# Y021.net
KiCad netlist of a schematic drawn in EAGLE
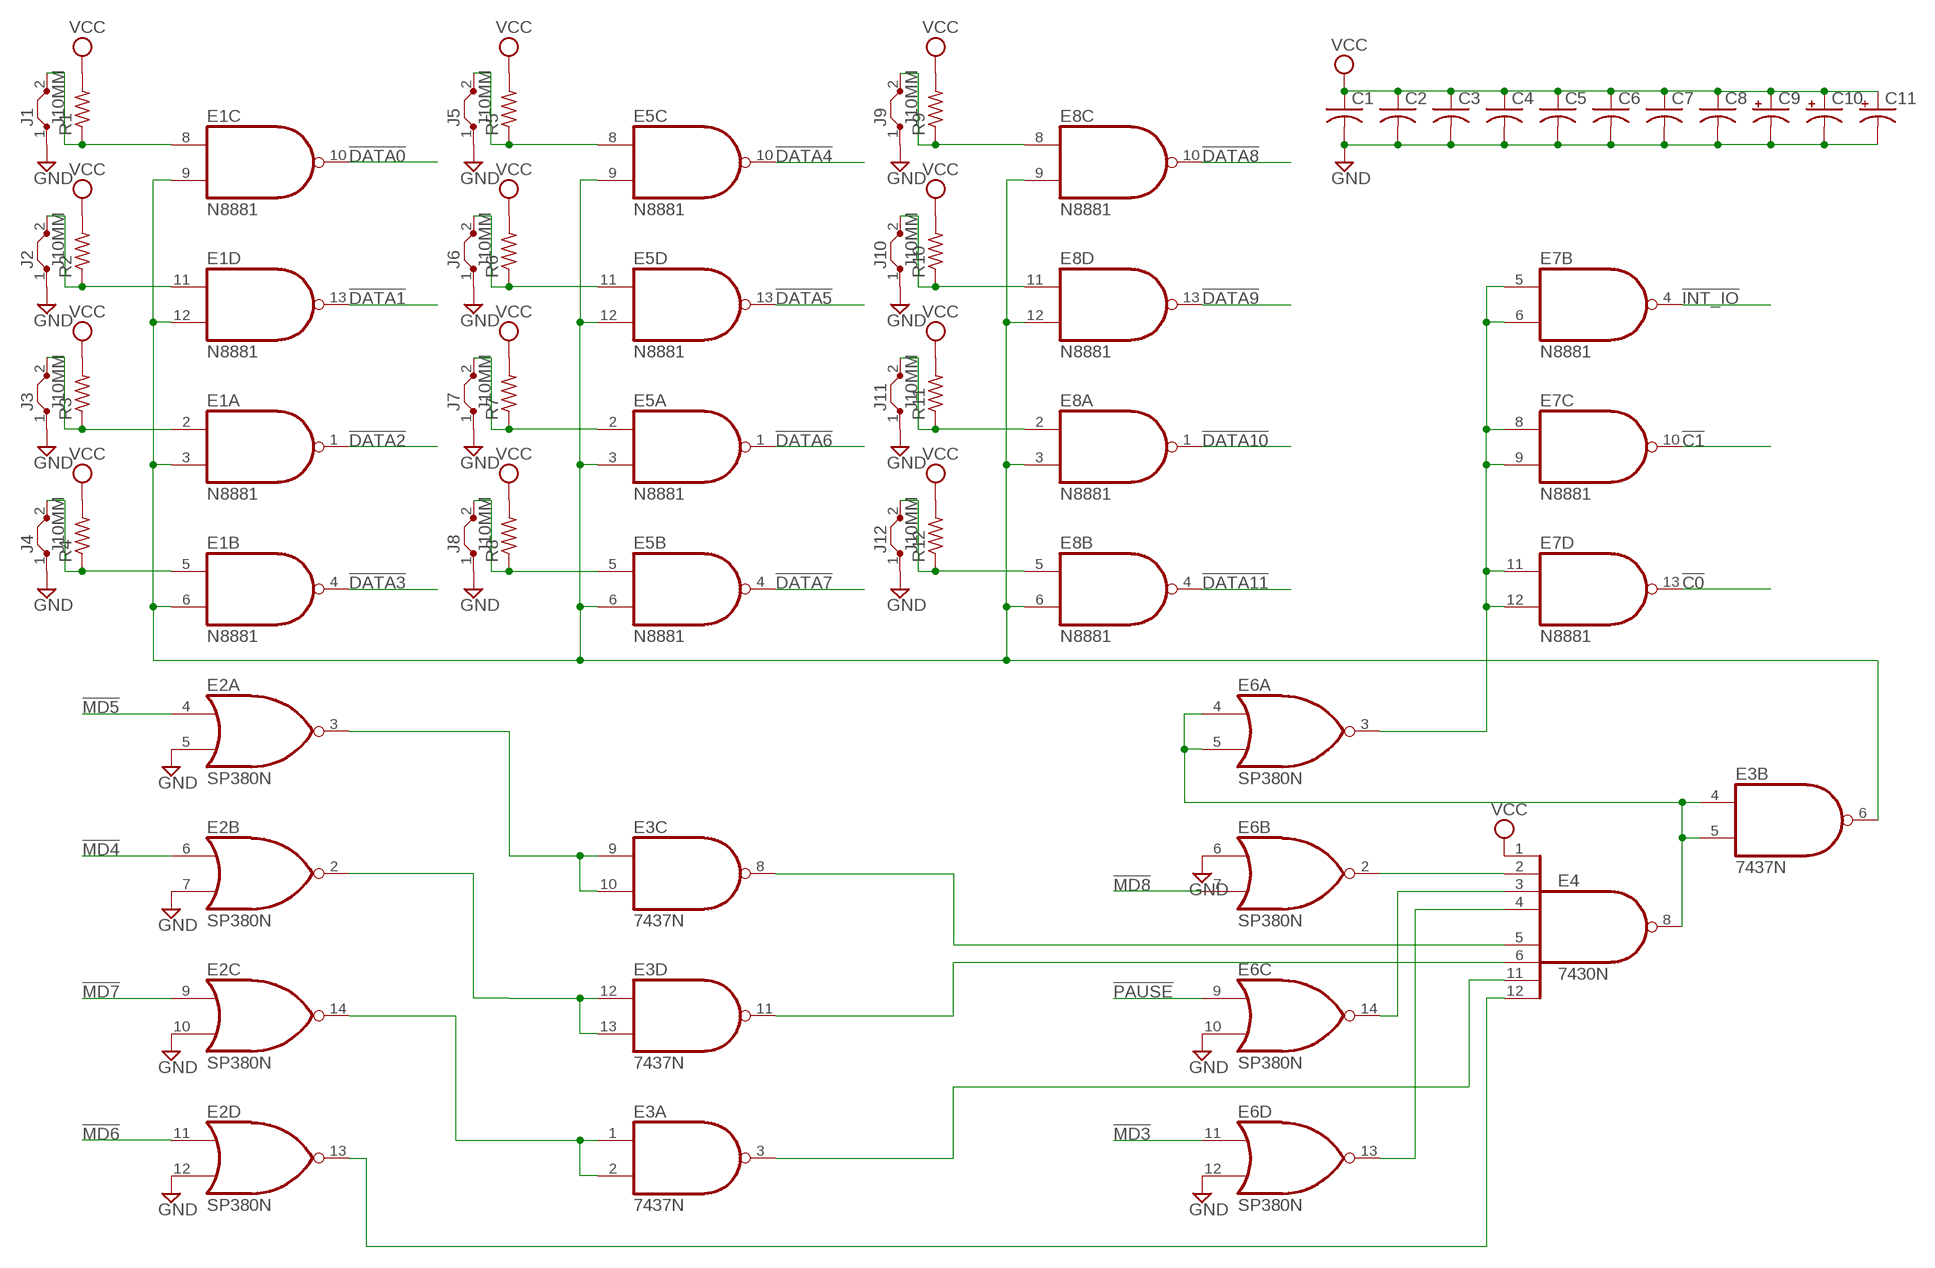
[diagram p0: schematic, sheet 1]
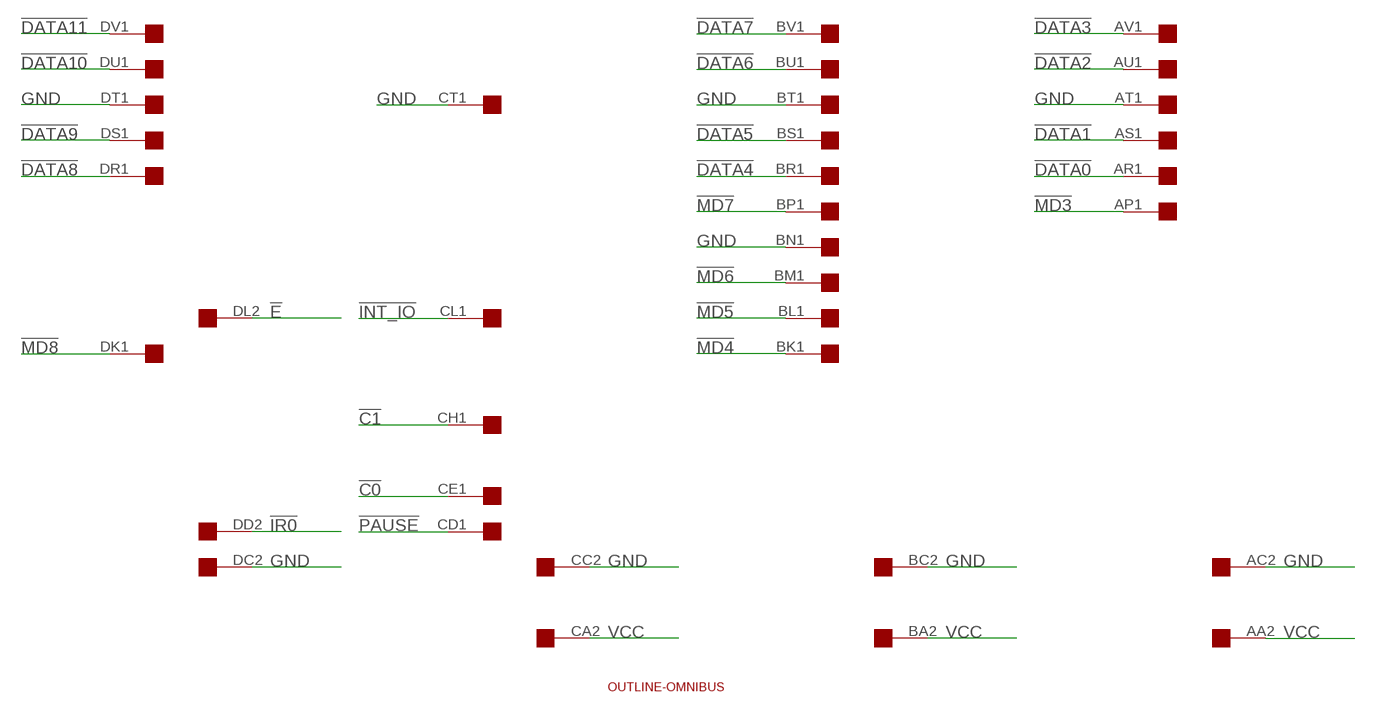
[diagram p1: schematic, sheet 2]

(export (version "E")
  (design (tool "Eeschema 10.0.6"))
  (components
    (comp (ref "C1")
      (value "C-US050-025X075")
      (footprint "eagle-import:C050-025X075")
      (libsource (lib "eagle-import") (part "C-US050-025X075"))
    )
    (comp (ref "C2")
      (value "C-US050-025X075")
      (footprint "eagle-import:C050-025X075")
      (libsource (lib "eagle-import") (part "C-US050-025X075"))
    )
    (comp (ref "C3")
      (value "C-US050-025X075")
      (footprint "eagle-import:C050-025X075")
      (libsource (lib "eagle-import") (part "C-US050-025X075"))
    )
    (comp (ref "C4")
      (value "C-US050-025X075")
      (footprint "eagle-import:C050-025X075")
      (libsource (lib "eagle-import") (part "C-US050-025X075"))
    )
    (comp (ref "C5")
      (value "C-US050-025X075")
      (footprint "eagle-import:C050-025X075")
      (libsource (lib "eagle-import") (part "C-US050-025X075"))
    )
    (comp (ref "C6")
      (value "C-US050-025X075")
      (footprint "eagle-import:C050-025X075")
      (libsource (lib "eagle-import") (part "C-US050-025X075"))
    )
    (comp (ref "C7")
      (value "C-US050-025X075")
      (footprint "eagle-import:C050-025X075")
      (libsource (lib "eagle-import") (part "C-US050-025X075"))
    )
    (comp (ref "C8")
      (value "C-US050-025X075")
      (footprint "eagle-import:C050-025X075")
      (libsource (lib "eagle-import") (part "C-US050-025X075"))
    )
    (comp (ref "C9")
      (value "CPOL-USE22-6AXIAL")
      (footprint "eagle-import:E22-6")
      (libsource (lib "eagle-import") (part "CPOL-USE22-6AXIAL"))
    )
    (comp (ref "C10")
      (value "CPOL-USE22-6AXIAL")
      (footprint "eagle-import:E22-6")
      (libsource (lib "eagle-import") (part "CPOL-USE22-6AXIAL"))
    )
    (comp (ref "C11")
      (value "CPOL-USE22-6AXIAL")
      (footprint "eagle-import:E22-6")
      (libsource (lib "eagle-import") (part "CPOL-USE22-6AXIAL"))
    )
    (comp (ref "E1")
      (value "N8881")
      (footprint "eagle-import:DIL14")
      (libsource (lib "eagle-import") (part "N8881N"))
    )
    (comp (ref "E2")
      (value "SP380N")
      (footprint "eagle-import:DIL14")
      (libsource (lib "eagle-import") (part "SP380N"))
    )
    (comp (ref "E3")
      (value "7437N")
      (footprint "eagle-import:DIL14")
      (libsource (lib "eagle-import") (part "7437N"))
    )
    (comp (ref "E4")
      (value "7430N")
      (footprint "eagle-import:DIL14")
      (libsource (lib "eagle-import") (part "7430N"))
    )
    (comp (ref "E5")
      (value "N8881")
      (footprint "eagle-import:DIL14")
      (libsource (lib "eagle-import") (part "N8881N"))
    )
    (comp (ref "E6")
      (value "SP380N")
      (footprint "eagle-import:DIL14")
      (libsource (lib "eagle-import") (part "SP380N"))
    )
    (comp (ref "E7")
      (value "N8881")
      (footprint "eagle-import:DIL14")
      (libsource (lib "eagle-import") (part "N8881N"))
    )
    (comp (ref "E8")
      (value "N8881")
      (footprint "eagle-import:DIL14")
      (libsource (lib "eagle-import") (part "N8881N"))
    )
    (comp (ref "J1")
      (value "J10MM")
      (footprint "eagle-import:10")
      (libsource (lib "eagle-import") (part "J10MM"))
    )
    (comp (ref "J2")
      (value "J10MM")
      (footprint "eagle-import:10")
      (libsource (lib "eagle-import") (part "J10MM"))
    )
    (comp (ref "J3")
      (value "J10MM")
      (footprint "eagle-import:10")
      (libsource (lib "eagle-import") (part "J10MM"))
    )
    (comp (ref "J4")
      (value "J10MM")
      (footprint "eagle-import:10")
      (libsource (lib "eagle-import") (part "J10MM"))
    )
    (comp (ref "J5")
      (value "J10MM")
      (footprint "eagle-import:10")
      (libsource (lib "eagle-import") (part "J10MM"))
    )
    (comp (ref "J6")
      (value "J10MM")
      (footprint "eagle-import:10")
      (libsource (lib "eagle-import") (part "J10MM"))
    )
    (comp (ref "J7")
      (value "J10MM")
      (footprint "eagle-import:10")
      (libsource (lib "eagle-import") (part "J10MM"))
    )
    (comp (ref "J8")
      (value "J10MM")
      (footprint "eagle-import:10")
      (libsource (lib "eagle-import") (part "J10MM"))
    )
    (comp (ref "J9")
      (value "J10MM")
      (footprint "eagle-import:10")
      (libsource (lib "eagle-import") (part "J10MM"))
    )
    (comp (ref "J10")
      (value "J10MM")
      (footprint "eagle-import:10")
      (libsource (lib "eagle-import") (part "J10MM"))
    )
    (comp (ref "J11")
      (value "J10MM")
      (footprint "eagle-import:10")
      (libsource (lib "eagle-import") (part "J10MM"))
    )
    (comp (ref "J12")
      (value "J10MM")
      (footprint "eagle-import:10")
      (libsource (lib "eagle-import") (part "J10MM"))
    )
    (comp (ref "R1")
      (value "R-US_0207/10")
      (footprint "eagle-import:0207_10")
      (libsource (lib "eagle-import") (part "R-US_0207/10"))
    )
    (comp (ref "R2")
      (value "R-US_0207/10")
      (footprint "eagle-import:0207_10")
      (libsource (lib "eagle-import") (part "R-US_0207/10"))
    )
    (comp (ref "R3")
      (value "R-US_0207/10")
      (footprint "eagle-import:0207_10")
      (libsource (lib "eagle-import") (part "R-US_0207/10"))
    )
    (comp (ref "R4")
      (value "R-US_0207/10")
      (footprint "eagle-import:0207_10")
      (libsource (lib "eagle-import") (part "R-US_0207/10"))
    )
    (comp (ref "R5")
      (value "R-US_0207/10")
      (footprint "eagle-import:0207_10")
      (libsource (lib "eagle-import") (part "R-US_0207/10"))
    )
    (comp (ref "R6")
      (value "R-US_0207/10")
      (footprint "eagle-import:0207_10")
      (libsource (lib "eagle-import") (part "R-US_0207/10"))
    )
    (comp (ref "R7")
      (value "R-US_0207/10")
      (footprint "eagle-import:0207_10")
      (libsource (lib "eagle-import") (part "R-US_0207/10"))
    )
    (comp (ref "R8")
      (value "R-US_0207/10")
      (footprint "eagle-import:0207_10")
      (libsource (lib "eagle-import") (part "R-US_0207/10"))
    )
    (comp (ref "R9")
      (value "R-US_0207/10")
      (footprint "eagle-import:0207_10")
      (libsource (lib "eagle-import") (part "R-US_0207/10"))
    )
    (comp (ref "R10")
      (value "R-US_0207/10")
      (footprint "eagle-import:0207_10")
      (libsource (lib "eagle-import") (part "R-US_0207/10"))
    )
    (comp (ref "R11")
      (value "R-US_0207/10")
      (footprint "eagle-import:0207_10")
      (libsource (lib "eagle-import") (part "R-US_0207/10"))
    )
    (comp (ref "R12")
      (value "R-US_0207/10")
      (footprint "eagle-import:0207_10")
      (libsource (lib "eagle-import") (part "R-US_0207/10"))
    )
    (comp (ref "U$1")
      (value "OUTLINE-OMNIBUS")
      (footprint "eagle-import:OMNIBUS")
      (libsource (lib "eagle-import") (part "OUTLINE-OMNIBUS"))
    )
    (comp (ref "U$2")
      (value "QUAD")
      (footprint "eagle-import:EDGE-CON8")
      (libsource (lib "eagle-import") (part "QUAD"))
    )
  )
  (nets
    (net (code "1") (name "GND") (class "Default")
      (node (ref "C1") (pin "2") (pinfunction "2_2") (pintype "passive"))
      (node (ref "C10") (pin "-") (pinfunction "-_-") (pintype "passive"))
      (node (ref "C11") (pin "-") (pinfunction "-_-") (pintype "passive"))
      (node (ref "C2") (pin "2") (pinfunction "2_2") (pintype "passive"))
      (node (ref "C3") (pin "2") (pinfunction "2_2") (pintype "passive"))
      (node (ref "C4") (pin "2") (pinfunction "2_2") (pintype "passive"))
      (node (ref "C5") (pin "2") (pinfunction "2_2") (pintype "passive"))
      (node (ref "C6") (pin "2") (pinfunction "2_2") (pintype "passive"))
      (node (ref "C7") (pin "2") (pinfunction "2_2") (pintype "passive"))
      (node (ref "C8") (pin "2") (pinfunction "2_2") (pintype "passive"))
      (node (ref "C9") (pin "-") (pinfunction "-_-") (pintype "passive"))
      (node (ref "E2") (pin "10") (pinfunction "I1_10") (pintype "input"))
      (node (ref "E2") (pin "12") (pinfunction "I1_12") (pintype "input"))
      (node (ref "E2") (pin "5") (pinfunction "I1_5") (pintype "input"))
      (node (ref "E2") (pin "7") (pinfunction "I1_7") (pintype "input"))
      (node (ref "E6") (pin "10") (pinfunction "I1_10") (pintype "input"))
      (node (ref "E6") (pin "12") (pinfunction "I1_12") (pintype "input"))
      (node (ref "E6") (pin "6") (pinfunction "I0_6") (pintype "input"))
      (node (ref "J1") (pin "1") (pinfunction "1_1") (pintype "passive"))
      (node (ref "J10") (pin "1") (pinfunction "1_1") (pintype "passive"))
      (node (ref "J11") (pin "1") (pinfunction "1_1") (pintype "passive"))
      (node (ref "J12") (pin "1") (pinfunction "1_1") (pintype "passive"))
      (node (ref "J2") (pin "1") (pinfunction "1_1") (pintype "passive"))
      (node (ref "J3") (pin "1") (pinfunction "1_1") (pintype "passive"))
      (node (ref "J4") (pin "1") (pinfunction "1_1") (pintype "passive"))
      (node (ref "J5") (pin "1") (pinfunction "1_1") (pintype "passive"))
      (node (ref "J6") (pin "1") (pinfunction "1_1") (pintype "passive"))
      (node (ref "J7") (pin "1") (pinfunction "1_1") (pintype "passive"))
      (node (ref "J8") (pin "1") (pinfunction "1_1") (pintype "passive"))
      (node (ref "J9") (pin "1") (pinfunction "1_1") (pintype "passive"))
      (node (ref "U$2") (pin "AC2") (pinfunction "1_AC2") (pintype "bidirectional"))
      (node (ref "U$2") (pin "AT1") (pinfunction "1_AT1") (pintype "bidirectional"))
      (node (ref "U$2") (pin "BC2") (pinfunction "1_BC2") (pintype "bidirectional"))
      (node (ref "U$2") (pin "BN1") (pinfunction "1_BN1") (pintype "bidirectional"))
      (node (ref "U$2") (pin "BT1") (pinfunction "1_BT1") (pintype "bidirectional"))
      (node (ref "U$2") (pin "CC2") (pinfunction "1_CC2") (pintype "bidirectional"))
      (node (ref "U$2") (pin "CT1") (pinfunction "1_CT1") (pintype "bidirectional"))
      (node (ref "U$2") (pin "DC2") (pinfunction "1_DC2") (pintype "bidirectional"))
      (node (ref "U$2") (pin "DT1") (pinfunction "1_DT1") (pintype "bidirectional"))
    )
    (net (code "2") (name "Net-(E1A-I0)") (class "Default")
      (node (ref "E1") (pin "2") (pinfunction "I0_2") (pintype "input"))
      (node (ref "J3") (pin "2") (pinfunction "2_2") (pintype "passive"))
      (node (ref "R3") (pin "1") (pinfunction "1_1") (pintype "passive"))
    )
    (net (code "3") (name "Net-(E1A-I1)") (class "Default")
      (node (ref "E1") (pin "12") (pinfunction "I1_12") (pintype "input"))
      (node (ref "E1") (pin "3") (pinfunction "I1_3") (pintype "input"))
      (node (ref "E1") (pin "6") (pinfunction "I1_6") (pintype "input"))
      (node (ref "E1") (pin "9") (pinfunction "I1_9") (pintype "input"))
      (node (ref "E3") (pin "6") (pinfunction "O_6") (pintype "output"))
      (node (ref "E5") (pin "12") (pinfunction "I1_12") (pintype "input"))
      (node (ref "E5") (pin "3") (pinfunction "I1_3") (pintype "input"))
      (node (ref "E5") (pin "6") (pinfunction "I1_6") (pintype "input"))
      (node (ref "E5") (pin "9") (pinfunction "I1_9") (pintype "input"))
      (node (ref "E8") (pin "12") (pinfunction "I1_12") (pintype "input"))
      (node (ref "E8") (pin "3") (pinfunction "I1_3") (pintype "input"))
      (node (ref "E8") (pin "6") (pinfunction "I1_6") (pintype "input"))
      (node (ref "E8") (pin "9") (pinfunction "I1_9") (pintype "input"))
    )
    (net (code "4") (name "Net-(E1B-I0)") (class "Default")
      (node (ref "E1") (pin "5") (pinfunction "I0_5") (pintype "input"))
      (node (ref "J4") (pin "2") (pinfunction "2_2") (pintype "passive"))
      (node (ref "R4") (pin "1") (pinfunction "1_1") (pintype "passive"))
    )
    (net (code "5") (name "Net-(E1C-I0)") (class "Default")
      (node (ref "E1") (pin "8") (pinfunction "I0_8") (pintype "input"))
      (node (ref "J1") (pin "2") (pinfunction "2_2") (pintype "passive"))
      (node (ref "R1") (pin "1") (pinfunction "1_1") (pintype "passive"))
    )
    (net (code "6") (name "Net-(E1D-I0)") (class "Default")
      (node (ref "E1") (pin "11") (pinfunction "I0_11") (pintype "input"))
      (node (ref "J2") (pin "2") (pinfunction "2_2") (pintype "passive"))
      (node (ref "R2") (pin "1") (pinfunction "1_1") (pintype "passive"))
    )
    (net (code "7") (name "Net-(E2A-O)") (class "Default")
      (node (ref "E2") (pin "3") (pinfunction "O_3") (pintype "output"))
      (node (ref "E3") (pin "10") (pinfunction "I1_10") (pintype "input"))
      (node (ref "E3") (pin "9") (pinfunction "I0_9") (pintype "input"))
    )
    (net (code "8") (name "Net-(E2B-O)") (class "Default")
      (node (ref "E2") (pin "2") (pinfunction "O_2") (pintype "output"))
      (node (ref "E3") (pin "12") (pinfunction "I0_12") (pintype "input"))
      (node (ref "E3") (pin "13") (pinfunction "I1_13") (pintype "input"))
    )
    (net (code "9") (name "Net-(E2C-O)") (class "Default")
      (node (ref "E2") (pin "14") (pinfunction "O_14") (pintype "output"))
      (node (ref "E3") (pin "1") (pinfunction "I0_1") (pintype "input"))
      (node (ref "E3") (pin "2") (pinfunction "I1_2") (pintype "input"))
    )
    (net (code "10") (name "Net-(E2D-O)") (class "Default")
      (node (ref "E2") (pin "13") (pinfunction "O_13") (pintype "output"))
      (node (ref "E4") (pin "12") (pinfunction "I7_12") (pintype "input"))
    )
    (net (code "11") (name "Net-(E3A-O)") (class "Default")
      (node (ref "E3") (pin "3") (pinfunction "O_3") (pintype "output"))
      (node (ref "E4") (pin "11") (pinfunction "I6_11") (pintype "input"))
    )
    (net (code "12") (name "Net-(E3B-I0)") (class "Default")
      (node (ref "E3") (pin "4") (pinfunction "I0_4") (pintype "input"))
      (node (ref "E3") (pin "5") (pinfunction "I1_5") (pintype "input"))
      (node (ref "E4") (pin "8") (pinfunction "O_8") (pintype "output"))
      (node (ref "E6") (pin "4") (pinfunction "I0_4") (pintype "input"))
      (node (ref "E6") (pin "5") (pinfunction "I1_5") (pintype "input"))
    )
    (net (code "13") (name "Net-(E3C-O)") (class "Default")
      (node (ref "E3") (pin "8") (pinfunction "O_8") (pintype "output"))
      (node (ref "E4") (pin "5") (pinfunction "I4_5") (pintype "input"))
    )
    (net (code "14") (name "Net-(E3D-O)") (class "Default")
      (node (ref "E3") (pin "11") (pinfunction "O_11") (pintype "output"))
      (node (ref "E4") (pin "6") (pinfunction "I5_6") (pintype "input"))
    )
    (net (code "15") (name "Net-(E4A-I1)") (class "Default")
      (node (ref "E4") (pin "2") (pinfunction "I1_2") (pintype "input"))
      (node (ref "E6") (pin "2") (pinfunction "O_2") (pintype "output"))
    )
    (net (code "16") (name "Net-(E4A-I2)") (class "Default")
      (node (ref "E4") (pin "3") (pinfunction "I2_3") (pintype "input"))
      (node (ref "E6") (pin "14") (pinfunction "O_14") (pintype "output"))
    )
    (net (code "17") (name "Net-(E4A-I3)") (class "Default")
      (node (ref "E4") (pin "4") (pinfunction "I3_4") (pintype "input"))
      (node (ref "E6") (pin "13") (pinfunction "O_13") (pintype "output"))
    )
    (net (code "18") (name "Net-(E5A-I0)") (class "Default")
      (node (ref "E5") (pin "2") (pinfunction "I0_2") (pintype "input"))
      (node (ref "J7") (pin "2") (pinfunction "2_2") (pintype "passive"))
      (node (ref "R7") (pin "1") (pinfunction "1_1") (pintype "passive"))
    )
    (net (code "19") (name "Net-(E5B-I0)") (class "Default")
      (node (ref "E5") (pin "5") (pinfunction "I0_5") (pintype "input"))
      (node (ref "J8") (pin "2") (pinfunction "2_2") (pintype "passive"))
      (node (ref "R8") (pin "1") (pinfunction "1_1") (pintype "passive"))
    )
    (net (code "20") (name "Net-(E5C-I0)") (class "Default")
      (node (ref "E5") (pin "8") (pinfunction "I0_8") (pintype "input"))
      (node (ref "J5") (pin "2") (pinfunction "2_2") (pintype "passive"))
      (node (ref "R5") (pin "1") (pinfunction "1_1") (pintype "passive"))
    )
    (net (code "21") (name "Net-(E5D-I0)") (class "Default")
      (node (ref "E5") (pin "11") (pinfunction "I0_11") (pintype "input"))
      (node (ref "J6") (pin "2") (pinfunction "2_2") (pintype "passive"))
      (node (ref "R6") (pin "1") (pinfunction "1_1") (pintype "passive"))
    )
    (net (code "22") (name "Net-(E6A-O)") (class "Default")
      (node (ref "E6") (pin "3") (pinfunction "O_3") (pintype "output"))
      (node (ref "E7") (pin "11") (pinfunction "I0_11") (pintype "input"))
      (node (ref "E7") (pin "12") (pinfunction "I1_12") (pintype "input"))
      (node (ref "E7") (pin "5") (pinfunction "I0_5") (pintype "input"))
      (node (ref "E7") (pin "6") (pinfunction "I1_6") (pintype "input"))
      (node (ref "E7") (pin "8") (pinfunction "I0_8") (pintype "input"))
      (node (ref "E7") (pin "9") (pinfunction "I1_9") (pintype "input"))
    )
    (net (code "23") (name "Net-(E8A-I0)") (class "Default")
      (node (ref "E8") (pin "2") (pinfunction "I0_2") (pintype "input"))
      (node (ref "J11") (pin "2") (pinfunction "2_2") (pintype "passive"))
      (node (ref "R11") (pin "1") (pinfunction "1_1") (pintype "passive"))
    )
    (net (code "24") (name "Net-(E8B-I0)") (class "Default")
      (node (ref "E8") (pin "5") (pinfunction "I0_5") (pintype "input"))
      (node (ref "J12") (pin "2") (pinfunction "2_2") (pintype "passive"))
      (node (ref "R12") (pin "1") (pinfunction "1_1") (pintype "passive"))
    )
    (net (code "25") (name "Net-(E8C-I0)") (class "Default")
      (node (ref "E8") (pin "8") (pinfunction "I0_8") (pintype "input"))
      (node (ref "J9") (pin "2") (pinfunction "2_2") (pintype "passive"))
      (node (ref "R9") (pin "1") (pinfunction "1_1") (pintype "passive"))
    )
    (net (code "26") (name "Net-(E8D-I0)") (class "Default")
      (node (ref "E8") (pin "11") (pinfunction "I0_11") (pintype "input"))
      (node (ref "J10") (pin "2") (pinfunction "2_2") (pintype "passive"))
      (node (ref "R10") (pin "1") (pinfunction "1_1") (pintype "passive"))
    )
    (net (code "27") (name "VCC") (class "Default")
      (node (ref "C1") (pin "1") (pinfunction "1_1") (pintype "passive"))
      (node (ref "C10") (pin "+") (pinfunction "+_+") (pintype "passive"))
      (node (ref "C11") (pin "+") (pinfunction "+_+") (pintype "passive"))
      (node (ref "C2") (pin "1") (pinfunction "1_1") (pintype "passive"))
      (node (ref "C3") (pin "1") (pinfunction "1_1") (pintype "passive"))
      (node (ref "C4") (pin "1") (pinfunction "1_1") (pintype "passive"))
      (node (ref "C5") (pin "1") (pinfunction "1_1") (pintype "passive"))
      (node (ref "C6") (pin "1") (pinfunction "1_1") (pintype "passive"))
      (node (ref "C7") (pin "1") (pinfunction "1_1") (pintype "passive"))
      (node (ref "C8") (pin "1") (pinfunction "1_1") (pintype "passive"))
      (node (ref "C9") (pin "+") (pinfunction "+_+") (pintype "passive"))
      (node (ref "E4") (pin "1") (pinfunction "I0_1") (pintype "input"))
      (node (ref "R1") (pin "2") (pinfunction "2_2") (pintype "passive"))
      (node (ref "R10") (pin "2") (pinfunction "2_2") (pintype "passive"))
      (node (ref "R11") (pin "2") (pinfunction "2_2") (pintype "passive"))
      (node (ref "R12") (pin "2") (pinfunction "2_2") (pintype "passive"))
      (node (ref "R2") (pin "2") (pinfunction "2_2") (pintype "passive"))
      (node (ref "R3") (pin "2") (pinfunction "2_2") (pintype "passive"))
      (node (ref "R4") (pin "2") (pinfunction "2_2") (pintype "passive"))
      (node (ref "R5") (pin "2") (pinfunction "2_2") (pintype "passive"))
      (node (ref "R6") (pin "2") (pinfunction "2_2") (pintype "passive"))
      (node (ref "R7") (pin "2") (pinfunction "2_2") (pintype "passive"))
      (node (ref "R8") (pin "2") (pinfunction "2_2") (pintype "passive"))
      (node (ref "R9") (pin "2") (pinfunction "2_2") (pintype "passive"))
      (node (ref "U$2") (pin "AA2") (pinfunction "1_AA2") (pintype "bidirectional"))
      (node (ref "U$2") (pin "BA2") (pinfunction "1_BA2") (pintype "bidirectional"))
      (node (ref "U$2") (pin "CA2") (pinfunction "1_CA2") (pintype "bidirectional"))
    )
    (net (code "28") (name "~{C0}") (class "Default")
      (node (ref "E7") (pin "13") (pinfunction "O_13") (pintype "open_collector"))
      (node (ref "U$2") (pin "CE1") (pinfunction "1_CE1") (pintype "bidirectional"))
    )
    (net (code "29") (name "~{C1}") (class "Default")
      (node (ref "E7") (pin "10") (pinfunction "O_10") (pintype "open_collector"))
      (node (ref "U$2") (pin "CH1") (pinfunction "1_CH1") (pintype "bidirectional"))
    )
    (net (code "30") (name "~{DATA0}") (class "Default")
      (node (ref "E1") (pin "10") (pinfunction "O_10") (pintype "open_collector"))
      (node (ref "U$2") (pin "AR1") (pinfunction "1_AR1") (pintype "bidirectional"))
    )
    (net (code "31") (name "~{DATA1}") (class "Default")
      (node (ref "E1") (pin "13") (pinfunction "O_13") (pintype "open_collector"))
      (node (ref "U$2") (pin "AS1") (pinfunction "1_AS1") (pintype "bidirectional"))
    )
    (net (code "32") (name "~{DATA2}") (class "Default")
      (node (ref "E1") (pin "1") (pinfunction "O_1") (pintype "open_collector"))
      (node (ref "U$2") (pin "AU1") (pinfunction "1_AU1") (pintype "bidirectional"))
    )
    (net (code "33") (name "~{DATA3}") (class "Default")
      (node (ref "E1") (pin "4") (pinfunction "O_4") (pintype "open_collector"))
      (node (ref "U$2") (pin "AV1") (pinfunction "1_AV1") (pintype "bidirectional"))
    )
    (net (code "34") (name "~{DATA4}") (class "Default")
      (node (ref "E5") (pin "10") (pinfunction "O_10") (pintype "open_collector"))
      (node (ref "U$2") (pin "BR1") (pinfunction "1_BR1") (pintype "bidirectional"))
    )
    (net (code "35") (name "~{DATA5}") (class "Default")
      (node (ref "E5") (pin "13") (pinfunction "O_13") (pintype "open_collector"))
      (node (ref "U$2") (pin "BS1") (pinfunction "1_BS1") (pintype "bidirectional"))
    )
    (net (code "36") (name "~{DATA6}") (class "Default")
      (node (ref "E5") (pin "1") (pinfunction "O_1") (pintype "open_collector"))
      (node (ref "U$2") (pin "BU1") (pinfunction "1_BU1") (pintype "bidirectional"))
    )
    (net (code "37") (name "~{DATA7}") (class "Default")
      (node (ref "E5") (pin "4") (pinfunction "O_4") (pintype "open_collector"))
      (node (ref "U$2") (pin "BV1") (pinfunction "1_BV1") (pintype "bidirectional"))
    )
    (net (code "38") (name "~{DATA8}") (class "Default")
      (node (ref "E8") (pin "10") (pinfunction "O_10") (pintype "open_collector"))
      (node (ref "U$2") (pin "DR1") (pinfunction "1_DR1") (pintype "bidirectional"))
    )
    (net (code "39") (name "~{DATA9}") (class "Default")
      (node (ref "E8") (pin "13") (pinfunction "O_13") (pintype "open_collector"))
      (node (ref "U$2") (pin "DS1") (pinfunction "1_DS1") (pintype "bidirectional"))
    )
    (net (code "40") (name "~{DATA10}") (class "Default")
      (node (ref "E8") (pin "1") (pinfunction "O_1") (pintype "open_collector"))
      (node (ref "U$2") (pin "DU1") (pinfunction "1_DU1") (pintype "bidirectional"))
    )
    (net (code "41") (name "~{DATA11}") (class "Default")
      (node (ref "E8") (pin "4") (pinfunction "O_4") (pintype "open_collector"))
      (node (ref "U$2") (pin "DV1") (pinfunction "1_DV1") (pintype "bidirectional"))
    )
    (net (code "42") (name "~{E}") (class "Default")
      (node (ref "U$2") (pin "DL2") (pinfunction "1_DL2") (pintype "bidirectional"))
    )
    (net (code "43") (name "~{INT_IO}") (class "Default")
      (node (ref "E7") (pin "4") (pinfunction "O_4") (pintype "open_collector"))
      (node (ref "U$2") (pin "CL1") (pinfunction "1_CL1") (pintype "bidirectional"))
    )
    (net (code "44") (name "~{IR0}") (class "Default")
      (node (ref "U$2") (pin "DD2") (pinfunction "1_DD2") (pintype "bidirectional"))
    )
    (net (code "45") (name "~{MD3}") (class "Default")
      (node (ref "E6") (pin "11") (pinfunction "I0_11") (pintype "input"))
      (node (ref "U$2") (pin "AP1") (pinfunction "1_AP1") (pintype "bidirectional"))
    )
    (net (code "46") (name "~{MD4}") (class "Default")
      (node (ref "E2") (pin "6") (pinfunction "I0_6") (pintype "input"))
      (node (ref "U$2") (pin "BK1") (pinfunction "1_BK1") (pintype "bidirectional"))
    )
    (net (code "47") (name "~{MD5}") (class "Default")
      (node (ref "E2") (pin "4") (pinfunction "I0_4") (pintype "input"))
      (node (ref "U$2") (pin "BL1") (pinfunction "1_BL1") (pintype "bidirectional"))
    )
    (net (code "48") (name "~{MD6}") (class "Default")
      (node (ref "E2") (pin "11") (pinfunction "I0_11") (pintype "input"))
      (node (ref "U$2") (pin "BM1") (pinfunction "1_BM1") (pintype "bidirectional"))
    )
    (net (code "49") (name "~{MD7}") (class "Default")
      (node (ref "E2") (pin "9") (pinfunction "I0_9") (pintype "input"))
      (node (ref "U$2") (pin "BP1") (pinfunction "1_BP1") (pintype "bidirectional"))
    )
    (net (code "50") (name "~{MD8}") (class "Default")
      (node (ref "E6") (pin "7") (pinfunction "I1_7") (pintype "input"))
      (node (ref "U$2") (pin "DK1") (pinfunction "1_DK1") (pintype "bidirectional"))
    )
    (net (code "51") (name "~{PAUSE}") (class "Default")
      (node (ref "E6") (pin "9") (pinfunction "I0_9") (pintype "input"))
      (node (ref "U$2") (pin "CD1") (pinfunction "1_CD1") (pintype "bidirectional"))
    )
  )
)
